# tritiled-0603.net
KiCad netlist of a schematic drawn in EAGLE
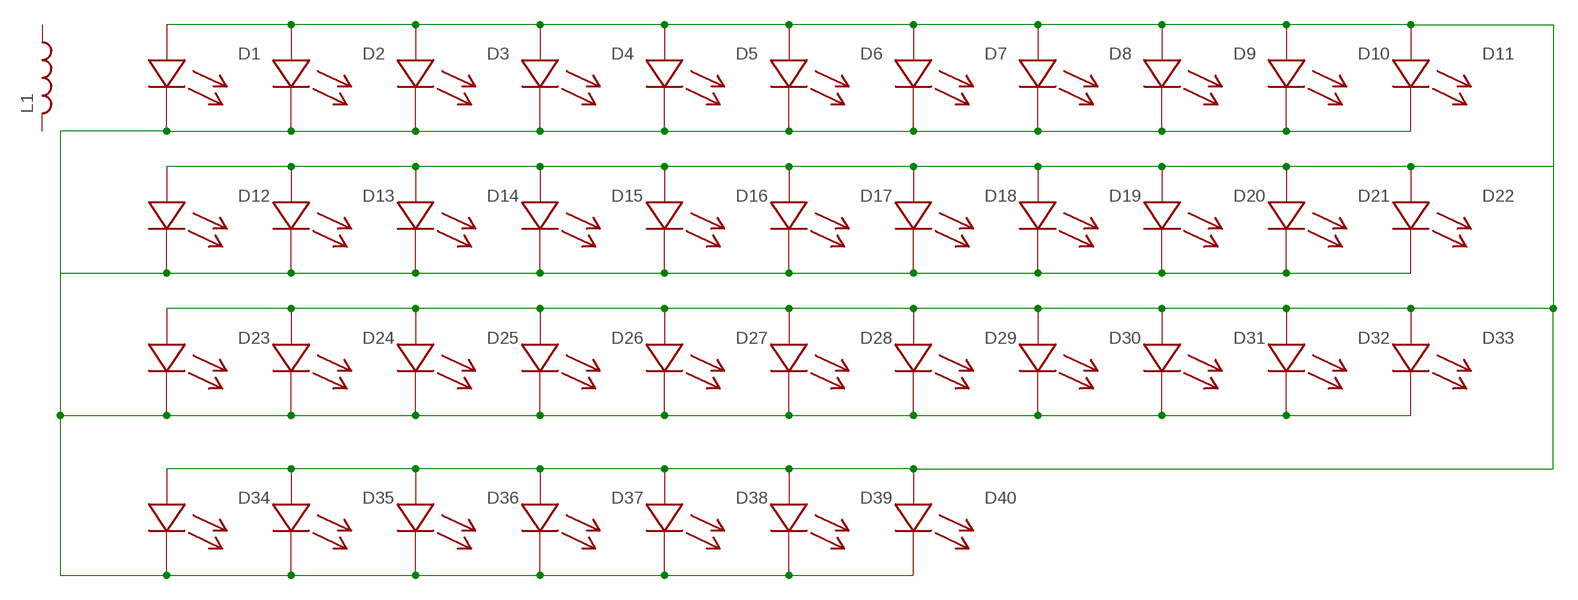
[diagram p0: schematic, sheet 1]

(export (version "E")
  (design (tool "Eeschema 10.0.6"))
  (components
    (comp (ref "D1")
      (value "LED")
      (footprint "eagle-import:LED_0603")
      (libsource (lib "eagle-import") (part "LED"))
    )
    (comp (ref "D2")
      (value "LED")
      (footprint "eagle-import:LED_0603")
      (libsource (lib "eagle-import") (part "LED"))
    )
    (comp (ref "D3")
      (value "LED")
      (footprint "eagle-import:LED_0603")
      (libsource (lib "eagle-import") (part "LED"))
    )
    (comp (ref "D4")
      (value "LED")
      (footprint "eagle-import:LED_0603")
      (libsource (lib "eagle-import") (part "LED"))
    )
    (comp (ref "D5")
      (value "LED")
      (footprint "eagle-import:LED_0603")
      (libsource (lib "eagle-import") (part "LED"))
    )
    (comp (ref "D6")
      (value "LED")
      (footprint "eagle-import:LED_0603")
      (libsource (lib "eagle-import") (part "LED"))
    )
    (comp (ref "D7")
      (value "LED")
      (footprint "eagle-import:LED_0603")
      (libsource (lib "eagle-import") (part "LED"))
    )
    (comp (ref "D8")
      (value "LED")
      (footprint "eagle-import:LED_0603")
      (libsource (lib "eagle-import") (part "LED"))
    )
    (comp (ref "D9")
      (value "LED")
      (footprint "eagle-import:LED_0603")
      (libsource (lib "eagle-import") (part "LED"))
    )
    (comp (ref "D10")
      (value "LED")
      (footprint "eagle-import:LED_0603")
      (libsource (lib "eagle-import") (part "LED"))
    )
    (comp (ref "D11")
      (value "LED")
      (footprint "eagle-import:LED_0603")
      (libsource (lib "eagle-import") (part "LED"))
    )
    (comp (ref "D12")
      (value "LED")
      (footprint "eagle-import:LED_0603")
      (libsource (lib "eagle-import") (part "LED"))
    )
    (comp (ref "D13")
      (value "LED")
      (footprint "eagle-import:LED_0603")
      (libsource (lib "eagle-import") (part "LED"))
    )
    (comp (ref "D14")
      (value "LED")
      (footprint "eagle-import:LED_0603")
      (libsource (lib "eagle-import") (part "LED"))
    )
    (comp (ref "D15")
      (value "LED")
      (footprint "eagle-import:LED_0603")
      (libsource (lib "eagle-import") (part "LED"))
    )
    (comp (ref "D16")
      (value "LED")
      (footprint "eagle-import:LED_0603")
      (libsource (lib "eagle-import") (part "LED"))
    )
    (comp (ref "D17")
      (value "LED")
      (footprint "eagle-import:LED_0603")
      (libsource (lib "eagle-import") (part "LED"))
    )
    (comp (ref "D18")
      (value "LED")
      (footprint "eagle-import:LED_0603")
      (libsource (lib "eagle-import") (part "LED"))
    )
    (comp (ref "D19")
      (value "LED")
      (footprint "eagle-import:LED_0603")
      (libsource (lib "eagle-import") (part "LED"))
    )
    (comp (ref "D20")
      (value "LED")
      (footprint "eagle-import:LED_0603")
      (libsource (lib "eagle-import") (part "LED"))
    )
    (comp (ref "D21")
      (value "LED")
      (footprint "eagle-import:LED_0603")
      (libsource (lib "eagle-import") (part "LED"))
    )
    (comp (ref "D22")
      (value "LED")
      (footprint "eagle-import:LED_0603")
      (libsource (lib "eagle-import") (part "LED"))
    )
    (comp (ref "D23")
      (value "LED")
      (footprint "eagle-import:LED_0603")
      (libsource (lib "eagle-import") (part "LED"))
    )
    (comp (ref "D24")
      (value "LED")
      (footprint "eagle-import:LED_0603")
      (libsource (lib "eagle-import") (part "LED"))
    )
    (comp (ref "D25")
      (value "LED")
      (footprint "eagle-import:LED_0603")
      (libsource (lib "eagle-import") (part "LED"))
    )
    (comp (ref "D26")
      (value "LED")
      (footprint "eagle-import:LED_0603")
      (libsource (lib "eagle-import") (part "LED"))
    )
    (comp (ref "D27")
      (value "LED")
      (footprint "eagle-import:LED_0603")
      (libsource (lib "eagle-import") (part "LED"))
    )
    (comp (ref "D28")
      (value "LED")
      (footprint "eagle-import:LED_0603")
      (libsource (lib "eagle-import") (part "LED"))
    )
    (comp (ref "D29")
      (value "LED")
      (footprint "eagle-import:LED_0603")
      (libsource (lib "eagle-import") (part "LED"))
    )
    (comp (ref "D30")
      (value "LED")
      (footprint "eagle-import:LED_0603")
      (libsource (lib "eagle-import") (part "LED"))
    )
    (comp (ref "D31")
      (value "LED")
      (footprint "eagle-import:LED_0603")
      (libsource (lib "eagle-import") (part "LED"))
    )
    (comp (ref "D32")
      (value "LED")
      (footprint "eagle-import:LED_0603")
      (libsource (lib "eagle-import") (part "LED"))
    )
    (comp (ref "D33")
      (value "LED")
      (footprint "eagle-import:LED_0603")
      (libsource (lib "eagle-import") (part "LED"))
    )
    (comp (ref "D34")
      (value "LED")
      (footprint "eagle-import:LED_0603")
      (libsource (lib "eagle-import") (part "LED"))
    )
    (comp (ref "D35")
      (value "LED")
      (footprint "eagle-import:LED_0603")
      (libsource (lib "eagle-import") (part "LED"))
    )
    (comp (ref "D36")
      (value "LED")
      (footprint "eagle-import:LED_0603")
      (libsource (lib "eagle-import") (part "LED"))
    )
    (comp (ref "D37")
      (value "LED")
      (footprint "eagle-import:LED_0603")
      (libsource (lib "eagle-import") (part "LED"))
    )
    (comp (ref "D38")
      (value "LED")
      (footprint "eagle-import:LED_0603")
      (libsource (lib "eagle-import") (part "LED"))
    )
    (comp (ref "D39")
      (value "LED")
      (footprint "eagle-import:LED_0603")
      (libsource (lib "eagle-import") (part "LED"))
    )
    (comp (ref "D40")
      (value "LED")
      (footprint "eagle-import:LED_0603")
      (libsource (lib "eagle-import") (part "LED"))
    )
    (comp (ref "L1")
      (value "SRR6028_INDUCTOR")
      (footprint "eagle-import:SRR6028_INDUCTOR")
      (libsource (lib "eagle-import") (part "SRR6028_INDUCTOR"))
    )
  )
  (nets
    (net (code "1") (name "Net-(D1-PadA)") (class "Default")
      (node (ref "D1") (pin "A") (pinfunction "A_A") (pintype "bidirectional"))
      (node (ref "D10") (pin "A") (pinfunction "A_A") (pintype "bidirectional"))
      (node (ref "D11") (pin "A") (pinfunction "A_A") (pintype "bidirectional"))
      (node (ref "D12") (pin "A") (pinfunction "A_A") (pintype "bidirectional"))
      (node (ref "D13") (pin "A") (pinfunction "A_A") (pintype "bidirectional"))
      (node (ref "D14") (pin "A") (pinfunction "A_A") (pintype "bidirectional"))
      (node (ref "D15") (pin "A") (pinfunction "A_A") (pintype "bidirectional"))
      (node (ref "D16") (pin "A") (pinfunction "A_A") (pintype "bidirectional"))
      (node (ref "D17") (pin "A") (pinfunction "A_A") (pintype "bidirectional"))
      (node (ref "D18") (pin "A") (pinfunction "A_A") (pintype "bidirectional"))
      (node (ref "D19") (pin "A") (pinfunction "A_A") (pintype "bidirectional"))
      (node (ref "D2") (pin "A") (pinfunction "A_A") (pintype "bidirectional"))
      (node (ref "D20") (pin "A") (pinfunction "A_A") (pintype "bidirectional"))
      (node (ref "D21") (pin "A") (pinfunction "A_A") (pintype "bidirectional"))
      (node (ref "D22") (pin "A") (pinfunction "A_A") (pintype "bidirectional"))
      (node (ref "D23") (pin "A") (pinfunction "A_A") (pintype "bidirectional"))
      (node (ref "D24") (pin "A") (pinfunction "A_A") (pintype "bidirectional"))
      (node (ref "D25") (pin "A") (pinfunction "A_A") (pintype "bidirectional"))
      (node (ref "D26") (pin "A") (pinfunction "A_A") (pintype "bidirectional"))
      (node (ref "D27") (pin "A") (pinfunction "A_A") (pintype "bidirectional"))
      (node (ref "D28") (pin "A") (pinfunction "A_A") (pintype "bidirectional"))
      (node (ref "D29") (pin "A") (pinfunction "A_A") (pintype "bidirectional"))
      (node (ref "D3") (pin "A") (pinfunction "A_A") (pintype "bidirectional"))
      (node (ref "D30") (pin "A") (pinfunction "A_A") (pintype "bidirectional"))
      (node (ref "D31") (pin "A") (pinfunction "A_A") (pintype "bidirectional"))
      (node (ref "D32") (pin "A") (pinfunction "A_A") (pintype "bidirectional"))
      (node (ref "D33") (pin "A") (pinfunction "A_A") (pintype "bidirectional"))
      (node (ref "D34") (pin "A") (pinfunction "A_A") (pintype "bidirectional"))
      (node (ref "D35") (pin "A") (pinfunction "A_A") (pintype "bidirectional"))
      (node (ref "D36") (pin "A") (pinfunction "A_A") (pintype "bidirectional"))
      (node (ref "D37") (pin "A") (pinfunction "A_A") (pintype "bidirectional"))
      (node (ref "D38") (pin "A") (pinfunction "A_A") (pintype "bidirectional"))
      (node (ref "D39") (pin "A") (pinfunction "A_A") (pintype "bidirectional"))
      (node (ref "D4") (pin "A") (pinfunction "A_A") (pintype "bidirectional"))
      (node (ref "D40") (pin "A") (pinfunction "A_A") (pintype "bidirectional"))
      (node (ref "D5") (pin "A") (pinfunction "A_A") (pintype "bidirectional"))
      (node (ref "D6") (pin "A") (pinfunction "A_A") (pintype "bidirectional"))
      (node (ref "D7") (pin "A") (pinfunction "A_A") (pintype "bidirectional"))
      (node (ref "D8") (pin "A") (pinfunction "A_A") (pintype "bidirectional"))
      (node (ref "D9") (pin "A") (pinfunction "A_A") (pintype "bidirectional"))
    )
    (net (code "2") (name "Net-(D1-PadC)") (class "Default")
      (node (ref "D1") (pin "C") (pinfunction "C_C") (pintype "bidirectional"))
      (node (ref "D10") (pin "C") (pinfunction "C_C") (pintype "bidirectional"))
      (node (ref "D11") (pin "C") (pinfunction "C_C") (pintype "bidirectional"))
      (node (ref "D12") (pin "C") (pinfunction "C_C") (pintype "bidirectional"))
      (node (ref "D13") (pin "C") (pinfunction "C_C") (pintype "bidirectional"))
      (node (ref "D14") (pin "C") (pinfunction "C_C") (pintype "bidirectional"))
      (node (ref "D15") (pin "C") (pinfunction "C_C") (pintype "bidirectional"))
      (node (ref "D16") (pin "C") (pinfunction "C_C") (pintype "bidirectional"))
      (node (ref "D17") (pin "C") (pinfunction "C_C") (pintype "bidirectional"))
      (node (ref "D18") (pin "C") (pinfunction "C_C") (pintype "bidirectional"))
      (node (ref "D19") (pin "C") (pinfunction "C_C") (pintype "bidirectional"))
      (node (ref "D2") (pin "C") (pinfunction "C_C") (pintype "bidirectional"))
      (node (ref "D20") (pin "C") (pinfunction "C_C") (pintype "bidirectional"))
      (node (ref "D21") (pin "C") (pinfunction "C_C") (pintype "bidirectional"))
      (node (ref "D22") (pin "C") (pinfunction "C_C") (pintype "bidirectional"))
      (node (ref "D23") (pin "C") (pinfunction "C_C") (pintype "bidirectional"))
      (node (ref "D24") (pin "C") (pinfunction "C_C") (pintype "bidirectional"))
      (node (ref "D25") (pin "C") (pinfunction "C_C") (pintype "bidirectional"))
      (node (ref "D26") (pin "C") (pinfunction "C_C") (pintype "bidirectional"))
      (node (ref "D27") (pin "C") (pinfunction "C_C") (pintype "bidirectional"))
      (node (ref "D28") (pin "C") (pinfunction "C_C") (pintype "bidirectional"))
      (node (ref "D29") (pin "C") (pinfunction "C_C") (pintype "bidirectional"))
      (node (ref "D3") (pin "C") (pinfunction "C_C") (pintype "bidirectional"))
      (node (ref "D30") (pin "C") (pinfunction "C_C") (pintype "bidirectional"))
      (node (ref "D31") (pin "C") (pinfunction "C_C") (pintype "bidirectional"))
      (node (ref "D32") (pin "C") (pinfunction "C_C") (pintype "bidirectional"))
      (node (ref "D33") (pin "C") (pinfunction "C_C") (pintype "bidirectional"))
      (node (ref "D34") (pin "C") (pinfunction "C_C") (pintype "bidirectional"))
      (node (ref "D35") (pin "C") (pinfunction "C_C") (pintype "bidirectional"))
      (node (ref "D36") (pin "C") (pinfunction "C_C") (pintype "bidirectional"))
      (node (ref "D37") (pin "C") (pinfunction "C_C") (pintype "bidirectional"))
      (node (ref "D38") (pin "C") (pinfunction "C_C") (pintype "bidirectional"))
      (node (ref "D39") (pin "C") (pinfunction "C_C") (pintype "bidirectional"))
      (node (ref "D4") (pin "C") (pinfunction "C_C") (pintype "bidirectional"))
      (node (ref "D40") (pin "C") (pinfunction "C_C") (pintype "bidirectional"))
      (node (ref "D5") (pin "C") (pinfunction "C_C") (pintype "bidirectional"))
      (node (ref "D6") (pin "C") (pinfunction "C_C") (pintype "bidirectional"))
      (node (ref "D7") (pin "C") (pinfunction "C_C") (pintype "bidirectional"))
      (node (ref "D8") (pin "C") (pinfunction "C_C") (pintype "bidirectional"))
      (node (ref "D9") (pin "C") (pinfunction "C_C") (pintype "bidirectional"))
    )
    (net (code "3") (name "unconnected-(L1-1-PadP$1)") (class "Default")
      (node (ref "L1") (pin "P$1") (pinfunction "1_P$1") (pintype "passive"))
    )
    (net (code "4") (name "unconnected-(L1-2-PadP$2)") (class "Default")
      (node (ref "L1") (pin "P$2") (pinfunction "2_P$2") (pintype "passive"))
    )
  )
)
